# 5V_Stepdown.net
KiCad netlist of a schematic drawn in EAGLE
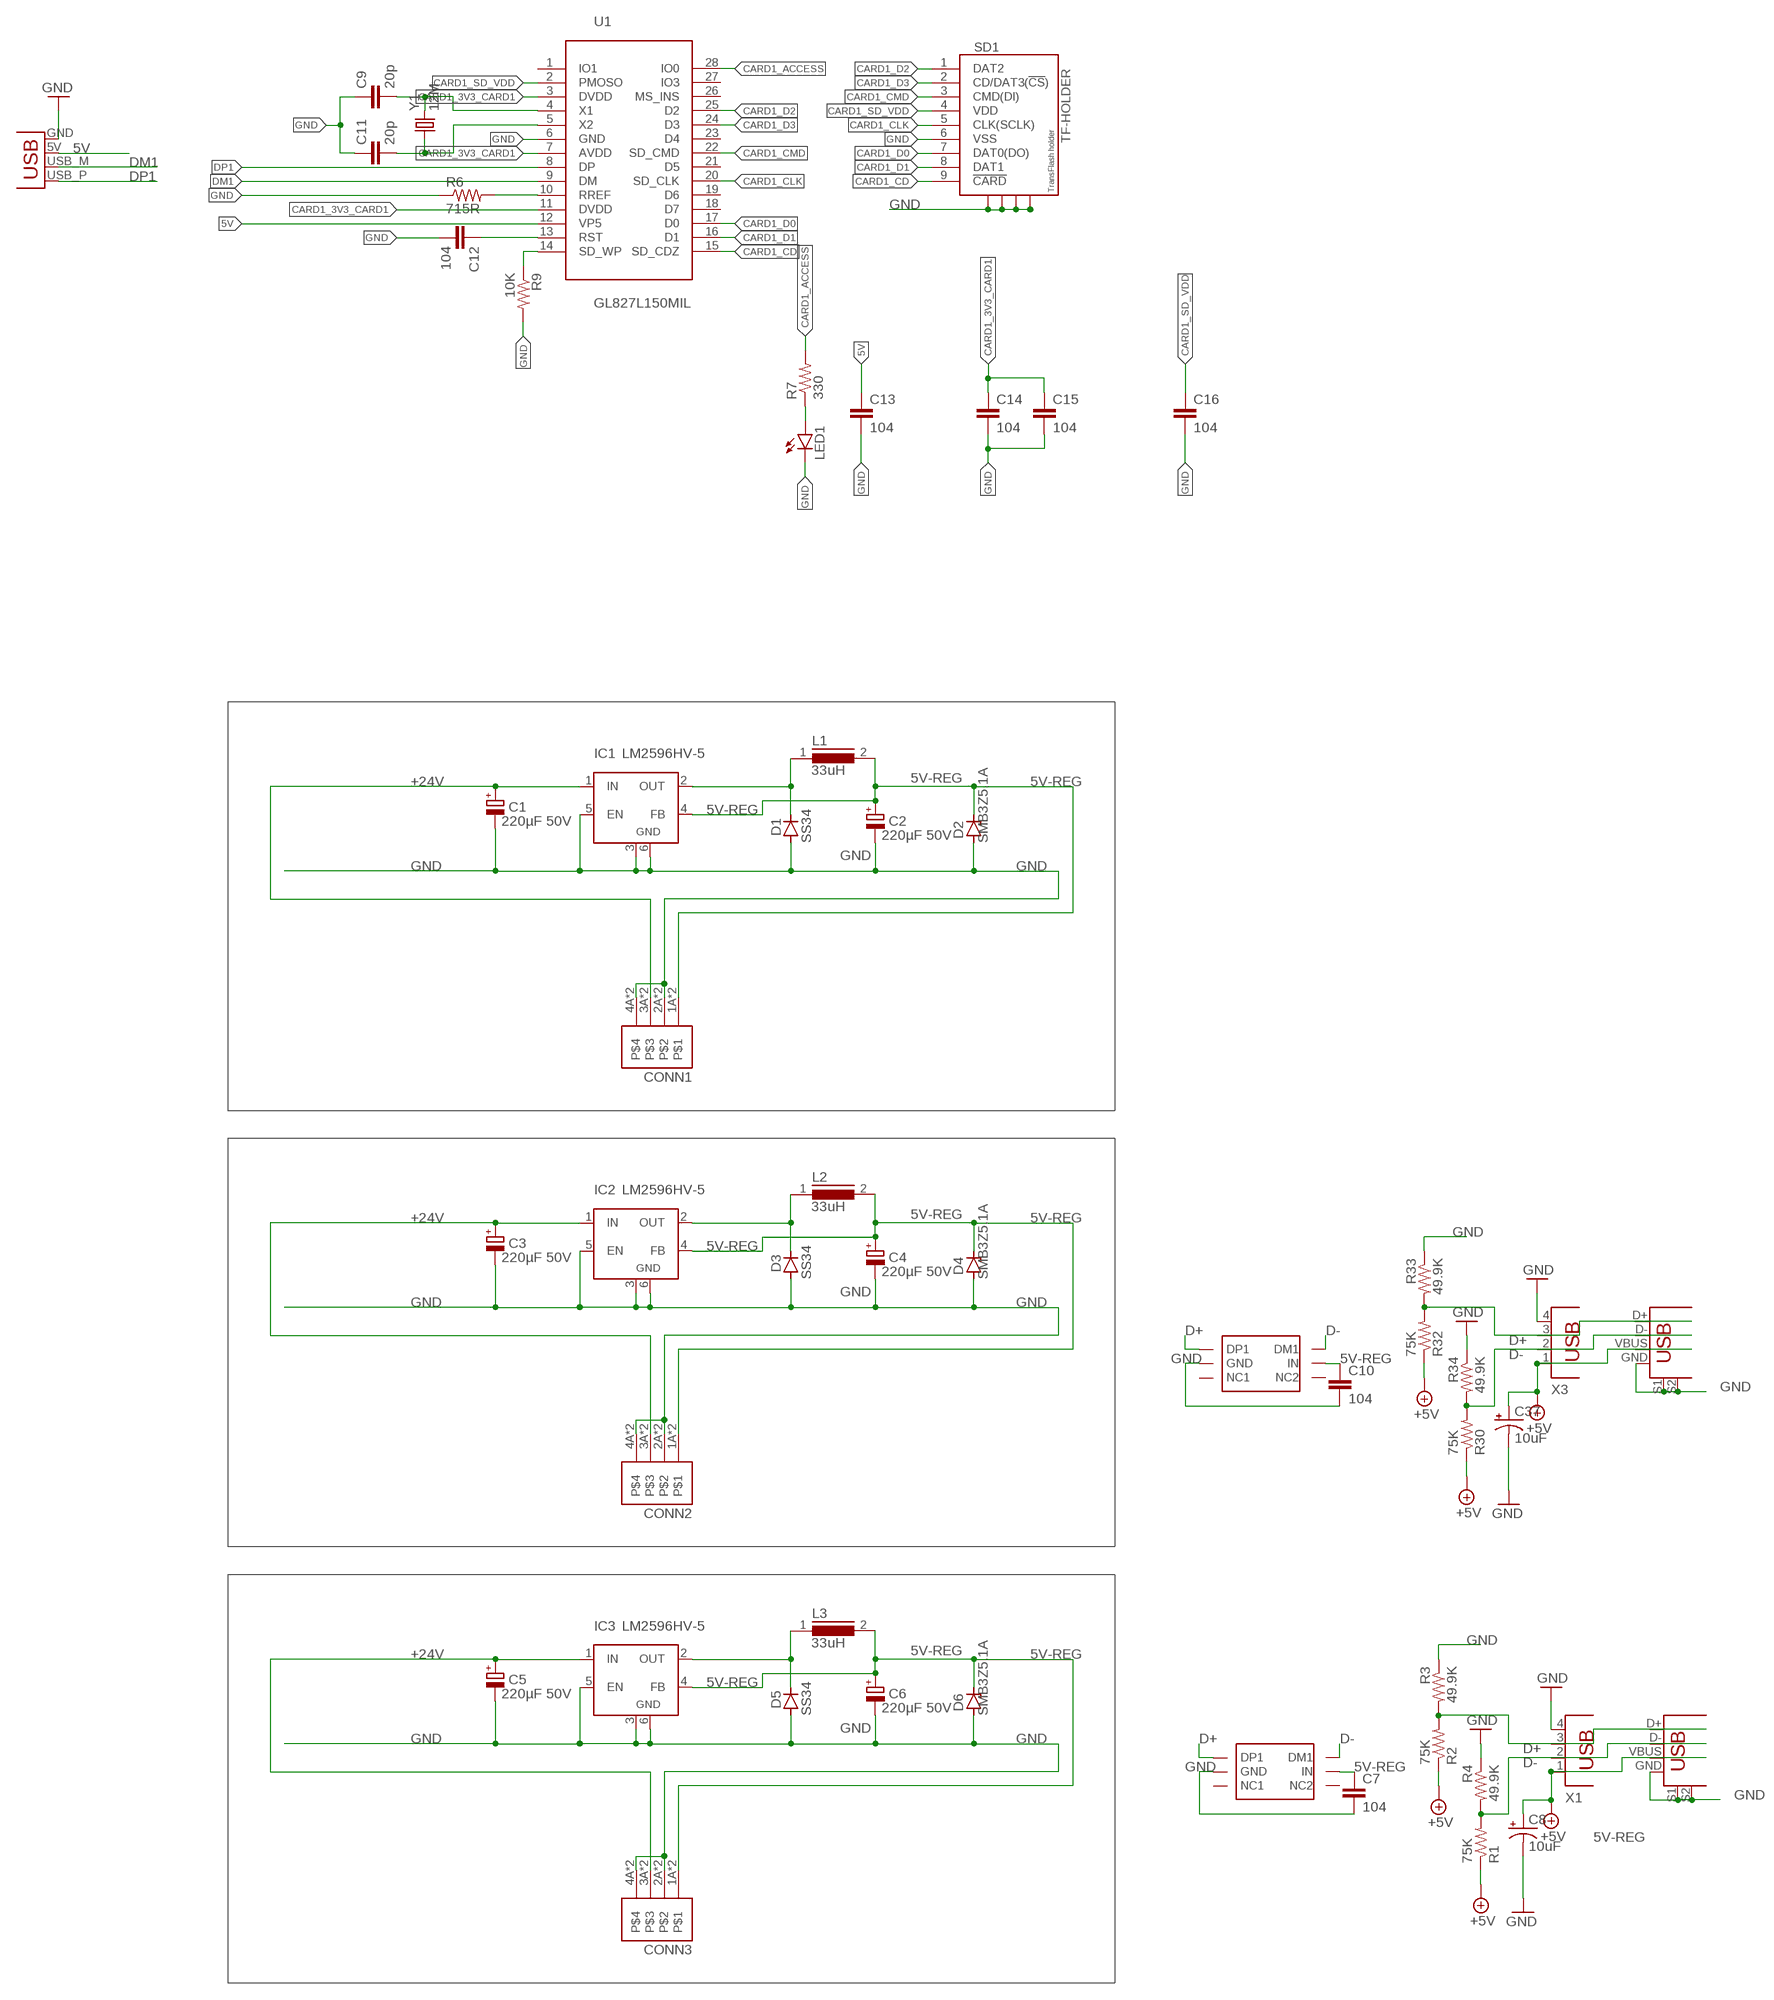
[diagram p0: schematic, sheet 1]

(export (version "E")
  (design (tool "Eeschema 10.0.6"))
  (components
    (comp (ref "C1")
      (value "220µF 50V")
      (footprint "eagle-import:PANASONIC_E")
      (libsource (lib "eagle-import") (part "CPOL-EUE"))
    )
    (comp (ref "C2")
      (value "220µF 50V")
      (footprint "eagle-import:PANASONIC_E")
      (libsource (lib "eagle-import") (part "CPOL-EUE"))
    )
    (comp (ref "C3")
      (value "220µF 50V")
      (footprint "eagle-import:PANASONIC_E")
      (libsource (lib "eagle-import") (part "CPOL-EUE"))
    )
    (comp (ref "C4")
      (value "220µF 50V")
      (footprint "eagle-import:PANASONIC_E")
      (libsource (lib "eagle-import") (part "CPOL-EUE"))
    )
    (comp (ref "C5")
      (value "220µF 50V")
      (footprint "eagle-import:PANASONIC_E")
      (libsource (lib "eagle-import") (part "CPOL-EUE"))
    )
    (comp (ref "C6")
      (value "220µF 50V")
      (footprint "eagle-import:PANASONIC_E")
      (libsource (lib "eagle-import") (part "CPOL-EUE"))
    )
    (comp (ref "C7")
      (value "104")
      (footprint "eagle-import:C1206")
      (libsource (lib "eagle-import") (part "C-EUC1206"))
    )
    (comp (ref "C8")
      (value "10uF")
      (footprint "eagle-import:EIA3216")
      (libsource (lib "eagle-import") (part "CAP_POL1206"))
    )
    (comp (ref "C9")
      (value "20p")
      (footprint "eagle-import:1206")
      (libsource (lib "eagle-import") (part "CAP1206"))
    )
    (comp (ref "C10")
      (value "104")
      (footprint "eagle-import:C1206")
      (libsource (lib "eagle-import") (part "C-EUC1206"))
    )
    (comp (ref "C11")
      (value "20p")
      (footprint "eagle-import:1206")
      (libsource (lib "eagle-import") (part "CAP1206"))
    )
    (comp (ref "C12")
      (value "104")
      (footprint "eagle-import:1206")
      (libsource (lib "eagle-import") (part "CAP1206"))
    )
    (comp (ref "C13")
      (value "104")
      (footprint "eagle-import:1206")
      (libsource (lib "eagle-import") (part "CAP1206"))
    )
    (comp (ref "C14")
      (value "104")
      (footprint "eagle-import:1206")
      (libsource (lib "eagle-import") (part "CAP1206"))
    )
    (comp (ref "C15")
      (value "104")
      (footprint "eagle-import:1206")
      (libsource (lib "eagle-import") (part "CAP1206"))
    )
    (comp (ref "C16")
      (value "104")
      (footprint "eagle-import:1206")
      (libsource (lib "eagle-import") (part "CAP1206"))
    )
    (comp (ref "C37")
      (value "10uF")
      (footprint "eagle-import:EIA3216")
      (libsource (lib "eagle-import") (part "CAP_POL1206"))
    )
    (comp (ref "CONN1")
      (value "WJ212R-THR-3.5-4")
      (footprint "eagle-import:WJ212R-THR-3.5-4")
      (libsource (lib "eagle-import") (part "WJ212R-THR-3.5-4"))
    )
    (comp (ref "CONN2")
      (value "WJ212R-THR-3.5-4")
      (footprint "eagle-import:WJ212R-THR-3.5-4")
      (libsource (lib "eagle-import") (part "WJ212R-THR-3.5-4"))
    )
    (comp (ref "CONN3")
      (value "WJ212R-THR-3.5-4")
      (footprint "eagle-import:WJ212R-THR-3.5-4")
      (libsource (lib "eagle-import") (part "WJ212R-THR-3.5-4"))
    )
    (comp (ref "D1")
      (value "SS34")
      (footprint "eagle-import:SOD87")
      (libsource (lib "eagle-import") (part "D-SOD-87"))
    )
    (comp (ref "D2")
      (value "SMB3Z5.1A")
      (footprint "eagle-import:SMB")
      (libsource (lib "eagle-import") (part "ZENER-DIODESMB"))
    )
    (comp (ref "D3")
      (value "SS34")
      (footprint "eagle-import:SOD87")
      (libsource (lib "eagle-import") (part "D-SOD-87"))
    )
    (comp (ref "D4")
      (value "SMB3Z5.1A")
      (footprint "eagle-import:SMB")
      (libsource (lib "eagle-import") (part "ZENER-DIODESMB"))
    )
    (comp (ref "D5")
      (value "SS34")
      (footprint "eagle-import:SOD87")
      (libsource (lib "eagle-import") (part "D-SOD-87"))
    )
    (comp (ref "D6")
      (value "SMB3Z5.1A")
      (footprint "eagle-import:SMB")
      (libsource (lib "eagle-import") (part "ZENER-DIODESMB"))
    )
    (comp (ref "IC1")
      (value "LM2596HV-5")
      (footprint "eagle-import:TO263-5")
      (libsource (lib "eagle-import") (part "LM2596S"))
    )
    (comp (ref "IC2")
      (value "LM2596HV-5")
      (footprint "eagle-import:TO263-5")
      (libsource (lib "eagle-import") (part "LM2596S"))
    )
    (comp (ref "IC3")
      (value "LM2596HV-5")
      (footprint "eagle-import:TO263-5")
      (libsource (lib "eagle-import") (part "LM2596S"))
    )
    (comp (ref "L1")
      (value "33uH")
      (footprint "eagle-import:DR127")
      (libsource (lib "eagle-import") (part "DR127"))
    )
    (comp (ref "L2")
      (value "33uH")
      (footprint "eagle-import:DR127")
      (libsource (lib "eagle-import") (part "DR127"))
    )
    (comp (ref "L3")
      (value "33uH")
      (footprint "eagle-import:DR127")
      (libsource (lib "eagle-import") (part "DR127"))
    )
    (comp (ref "LED1")
      (value "LED3MM")
      (footprint "eagle-import:LED3MM")
      (libsource (lib "eagle-import") (part "LED3MM"))
    )
    (comp (ref "R1")
      (value "75K")
      (footprint "eagle-import:M1206")
      (libsource (lib "eagle-import") (part "R-US_M1206"))
    )
    (comp (ref "R2")
      (value "75K")
      (footprint "eagle-import:M1206")
      (libsource (lib "eagle-import") (part "R-US_M1206"))
    )
    (comp (ref "R3")
      (value "49.9K")
      (footprint "eagle-import:M1206")
      (libsource (lib "eagle-import") (part "R-US_M1206"))
    )
    (comp (ref "R4")
      (value "49.9K")
      (footprint "eagle-import:M1206")
      (libsource (lib "eagle-import") (part "R-US_M1206"))
    )
    (comp (ref "R6")
      (value "715R")
      (footprint "eagle-import:1206")
      (libsource (lib "eagle-import") (part "RESISTOR1206"))
    )
    (comp (ref "R7")
      (value "330")
      (footprint "eagle-import:1206")
      (libsource (lib "eagle-import") (part "RESISTOR1206"))
    )
    (comp (ref "R9")
      (value "10K")
      (footprint "eagle-import:1206")
      (libsource (lib "eagle-import") (part "RESISTOR1206"))
    )
    (comp (ref "R30")
      (value "75K")
      (footprint "eagle-import:M1206")
      (libsource (lib "eagle-import") (part "R-US_M1206"))
    )
    (comp (ref "R32")
      (value "75K")
      (footprint "eagle-import:M1206")
      (libsource (lib "eagle-import") (part "R-US_M1206"))
    )
    (comp (ref "R33")
      (value "49.9K")
      (footprint "eagle-import:M1206")
      (libsource (lib "eagle-import") (part "R-US_M1206"))
    )
    (comp (ref "R34")
      (value "49.9K")
      (footprint "eagle-import:M1206")
      (libsource (lib "eagle-import") (part "R-US_M1206"))
    )
    (comp (ref "SD1")
      (value "TF-HOLDER")
      (footprint "eagle-import:TF-PULL")
      (libsource (lib "eagle-import") (part "TF-HOLDER"))
    )
    (comp (ref "U$1")
      (value "TPS2514")
      (footprint "eagle-import:TPS2514")
      (libsource (lib "eagle-import") (part "TPS2514"))
    )
    (comp (ref "U$2")
      (value "TPS2514")
      (footprint "eagle-import:TPS2514")
      (libsource (lib "eagle-import") (part "TPS2514"))
    )
    (comp (ref "U$3")
      (value "USB+SHIELDUSB-A-S-NOSILK-FEMALE")
      (footprint "eagle-import:USB-A-S-NOSILK-FEMALE")
      (libsource (lib "eagle-import") (part "USB+SHIELDUSB-A-S-NOSILK-FEMALE"))
    )
    (comp (ref "U$4")
      (value "USB+SHIELDUSB-A-S-NOSILK-FEMALE")
      (footprint "eagle-import:USB-A-S-NOSILK-FEMALE")
      (libsource (lib "eagle-import") (part "USB+SHIELDUSB-A-S-NOSILK-FEMALE"))
    )
    (comp (ref "U1")
      (value "GL827L150MIL")
      (footprint "eagle-import:SSOP28-39")
      (libsource (lib "eagle-import") (part "GL827L150MIL"))
    )
    (comp (ref "X1")
      (value "PN87520")
      (footprint "eagle-import:PN87520")
      (libsource (lib "eagle-import") (part "PN87520"))
    )
    (comp (ref "X2")
      (value "USBPCB")
      (footprint "eagle-import:USB-A-PCB")
      (libsource (lib "eagle-import") (part "USBPCB"))
    )
    (comp (ref "X3")
      (value "PN87520")
      (footprint "eagle-import:PN87520")
      (libsource (lib "eagle-import") (part "PN87520"))
    )
    (comp (ref "Y1")
      (value "12M")
      (footprint "eagle-import:HC49US")
      (libsource (lib "eagle-import") (part "CRYSTAL2HC49US"))
    )
  )
  (nets
    (net (code "1") (name "+24V") (class "Default")
      (node (ref "C1") (pin "+") (pinfunction "+_+") (pintype "passive"))
      (node (ref "C3") (pin "+") (pinfunction "+_+") (pintype "passive"))
      (node (ref "C5") (pin "+") (pinfunction "+_+") (pintype "passive"))
      (node (ref "CONN1") (pin "3A") (pinfunction "P$3_3A") (pintype "bidirectional"))
      (node (ref "CONN1") (pin "3B") (pinfunction "P$3_3B") (pintype "bidirectional"))
      (node (ref "CONN2") (pin "3A") (pinfunction "P$3_3A") (pintype "bidirectional"))
      (node (ref "CONN2") (pin "3B") (pinfunction "P$3_3B") (pintype "bidirectional"))
      (node (ref "CONN3") (pin "3A") (pinfunction "P$3_3A") (pintype "bidirectional"))
      (node (ref "CONN3") (pin "3B") (pinfunction "P$3_3B") (pintype "bidirectional"))
      (node (ref "IC1") (pin "1") (pinfunction "IN_1") (pintype "input"))
      (node (ref "IC2") (pin "1") (pinfunction "IN_1") (pintype "input"))
      (node (ref "IC3") (pin "1") (pinfunction "IN_1") (pintype "input"))
    )
    (net (code "2") (name "5V") (class "Default")
      (node (ref "C13") (pin "1") (pinfunction "1_1") (pintype "passive"))
      (node (ref "U1") (pin "12") (pinfunction "VP5_12") (pintype "bidirectional"))
      (node (ref "X2") (pin "5V") (pinfunction "VBUS_5V") (pintype "bidirectional"))
    )
    (net (code "3") (name "5V-REG") (class "Default")
      (node (ref "C10") (pin "1") (pinfunction "1_1") (pintype "passive"))
      (node (ref "C2") (pin "+") (pinfunction "+_+") (pintype "passive"))
      (node (ref "C37") (pin "A") (pinfunction "+_A") (pintype "passive"))
      (node (ref "C4") (pin "+") (pinfunction "+_+") (pintype "passive"))
      (node (ref "C6") (pin "+") (pinfunction "+_+") (pintype "passive"))
      (node (ref "C7") (pin "1") (pinfunction "1_1") (pintype "passive"))
      (node (ref "C8") (pin "A") (pinfunction "+_A") (pintype "passive"))
      (node (ref "CONN1") (pin "1A") (pinfunction "P$1_1A") (pintype "bidirectional"))
      (node (ref "CONN1") (pin "1B") (pinfunction "P$1_1B") (pintype "bidirectional"))
      (node (ref "CONN2") (pin "1A") (pinfunction "P$1_1A") (pintype "bidirectional"))
      (node (ref "CONN2") (pin "1B") (pinfunction "P$1_1B") (pintype "bidirectional"))
      (node (ref "CONN3") (pin "1A") (pinfunction "P$1_1A") (pintype "bidirectional"))
      (node (ref "CONN3") (pin "1B") (pinfunction "P$1_1B") (pintype "bidirectional"))
      (node (ref "D2") (pin "C") (pinfunction "C_C") (pintype "passive"))
      (node (ref "D4") (pin "C") (pinfunction "C_C") (pintype "passive"))
      (node (ref "D6") (pin "C") (pinfunction "C_C") (pintype "passive"))
      (node (ref "IC1") (pin "4") (pinfunction "FB_4") (pintype "input"))
      (node (ref "IC2") (pin "4") (pinfunction "FB_4") (pintype "input"))
      (node (ref "IC3") (pin "4") (pinfunction "FB_4") (pintype "input"))
      (node (ref "L1") (pin "2") (pinfunction "2_2") (pintype "passive"))
      (node (ref "L2") (pin "2") (pinfunction "2_2") (pintype "passive"))
      (node (ref "L3") (pin "2") (pinfunction "2_2") (pintype "passive"))
      (node (ref "R1") (pin "1") (pinfunction "1_1") (pintype "passive"))
      (node (ref "R2") (pin "1") (pinfunction "1_1") (pintype "passive"))
      (node (ref "R30") (pin "1") (pinfunction "1_1") (pintype "passive"))
      (node (ref "R32") (pin "1") (pinfunction "1_1") (pintype "passive"))
      (node (ref "U$1") (pin "IN") (pinfunction "IN_IN") (pintype "bidirectional"))
      (node (ref "U$2") (pin "IN") (pinfunction "IN_IN") (pintype "bidirectional"))
      (node (ref "U$3") (pin "VBUS") (pinfunction "VBUS_VBUS") (pintype "bidirectional"))
      (node (ref "U$4") (pin "VBUS") (pinfunction "VBUS_VBUS") (pintype "bidirectional"))
      (node (ref "X1") (pin "1") (pinfunction "1_1") (pintype "passive"))
      (node (ref "X3") (pin "1") (pinfunction "1_1") (pintype "passive"))
    )
    (net (code "4") (name "CARD1_3V3_CARD1") (class "Default")
      (node (ref "C14") (pin "1") (pinfunction "1_1") (pintype "passive"))
      (node (ref "C15") (pin "1") (pinfunction "1_1") (pintype "passive"))
      (node (ref "U1") (pin "11") (pinfunction "DVDD_11") (pintype "bidirectional"))
      (node (ref "U1") (pin "3") (pinfunction "DVDD_3") (pintype "bidirectional"))
      (node (ref "U1") (pin "7") (pinfunction "AVDD_7") (pintype "bidirectional"))
    )
    (net (code "5") (name "CARD1_ACCESS") (class "Default")
      (node (ref "R7") (pin "2") (pinfunction "2_2") (pintype "passive"))
      (node (ref "U1") (pin "28") (pinfunction "IO0_28") (pintype "bidirectional"))
    )
    (net (code "6") (name "CARD1_CD") (class "Default")
      (node (ref "SD1") (pin "9") (pinfunction "~{CARD}_9") (pintype "passive"))
      (node (ref "U1") (pin "15") (pinfunction "SD_CDZ_15") (pintype "bidirectional"))
    )
    (net (code "7") (name "CARD1_CLK") (class "Default")
      (node (ref "SD1") (pin "5") (pinfunction "CLK(SCLK)_5") (pintype "input"))
      (node (ref "U1") (pin "20") (pinfunction "SD_CLK_20") (pintype "bidirectional"))
    )
    (net (code "8") (name "CARD1_CMD") (class "Default")
      (node (ref "SD1") (pin "3") (pinfunction "CMD(DI)_3") (pintype "bidirectional"))
      (node (ref "U1") (pin "22") (pinfunction "SD_CMD_22") (pintype "bidirectional"))
    )
    (net (code "9") (name "CARD1_D0") (class "Default")
      (node (ref "SD1") (pin "7") (pinfunction "DAT0(DO)_7") (pintype "bidirectional"))
      (node (ref "U1") (pin "17") (pinfunction "D0_17") (pintype "bidirectional"))
    )
    (net (code "10") (name "CARD1_D1") (class "Default")
      (node (ref "SD1") (pin "8") (pinfunction "DAT1_8") (pintype "bidirectional"))
      (node (ref "U1") (pin "16") (pinfunction "D1_16") (pintype "bidirectional"))
    )
    (net (code "11") (name "CARD1_D2") (class "Default")
      (node (ref "SD1") (pin "1") (pinfunction "DAT2_1") (pintype "bidirectional"))
      (node (ref "U1") (pin "25") (pinfunction "D2_25") (pintype "bidirectional"))
    )
    (net (code "12") (name "CARD1_D3") (class "Default")
      (node (ref "SD1") (pin "2") (pinfunction "CD/DAT3(~{CS})_2") (pintype "bidirectional"))
      (node (ref "U1") (pin "24") (pinfunction "D3_24") (pintype "bidirectional"))
    )
    (net (code "13") (name "CARD1_SD_VDD") (class "Default")
      (node (ref "C16") (pin "1") (pinfunction "1_1") (pintype "passive"))
      (node (ref "SD1") (pin "4") (pinfunction "VDD_4") (pintype "power_in"))
      (node (ref "U1") (pin "2") (pinfunction "PMOSO_2") (pintype "bidirectional"))
    )
    (net (code "14") (name "D+") (class "Default")
      (node (ref "R2") (pin "2") (pinfunction "2_2") (pintype "passive"))
      (node (ref "R3") (pin "2") (pinfunction "2_2") (pintype "passive"))
      (node (ref "R32") (pin "2") (pinfunction "2_2") (pintype "passive"))
      (node (ref "R33") (pin "2") (pinfunction "2_2") (pintype "passive"))
      (node (ref "U$1") (pin "DP1") (pinfunction "DP1_DP1") (pintype "bidirectional"))
      (node (ref "U$2") (pin "DP1") (pinfunction "DP1_DP1") (pintype "bidirectional"))
      (node (ref "U$3") (pin "D+") (pinfunction "D+_D+") (pintype "bidirectional"))
      (node (ref "U$4") (pin "D+") (pinfunction "D+_D+") (pintype "bidirectional"))
      (node (ref "X1") (pin "3") (pinfunction "3_3") (pintype "passive"))
      (node (ref "X3") (pin "3") (pinfunction "3_3") (pintype "passive"))
    )
    (net (code "15") (name "D-") (class "Default")
      (node (ref "R1") (pin "2") (pinfunction "2_2") (pintype "passive"))
      (node (ref "R30") (pin "2") (pinfunction "2_2") (pintype "passive"))
      (node (ref "R34") (pin "2") (pinfunction "2_2") (pintype "passive"))
      (node (ref "R4") (pin "2") (pinfunction "2_2") (pintype "passive"))
      (node (ref "U$1") (pin "DM1") (pinfunction "DM1_DM1") (pintype "bidirectional"))
      (node (ref "U$2") (pin "DM1") (pinfunction "DM1_DM1") (pintype "bidirectional"))
      (node (ref "U$3") (pin "D-") (pinfunction "D-_D-") (pintype "bidirectional"))
      (node (ref "U$4") (pin "D-") (pinfunction "D-_D-") (pintype "bidirectional"))
      (node (ref "X1") (pin "2") (pinfunction "2_2") (pintype "passive"))
      (node (ref "X3") (pin "2") (pinfunction "2_2") (pintype "passive"))
    )
    (net (code "16") (name "DM1") (class "Default")
      (node (ref "U1") (pin "9") (pinfunction "DM_9") (pintype "bidirectional"))
      (node (ref "X2") (pin "USB_M") (pinfunction "D-_USB_M") (pintype "bidirectional"))
    )
    (net (code "17") (name "DP1") (class "Default")
      (node (ref "U1") (pin "8") (pinfunction "DP_8") (pintype "bidirectional"))
      (node (ref "X2") (pin "USB_P") (pinfunction "D+_USB_P") (pintype "bidirectional"))
    )
    (net (code "18") (name "GND") (class "Default")
      (node (ref "C1") (pin "-") (pinfunction "-_-") (pintype "passive"))
      (node (ref "C10") (pin "2") (pinfunction "2_2") (pintype "passive"))
      (node (ref "C11") (pin "1") (pinfunction "1_1") (pintype "passive"))
      (node (ref "C12") (pin "2") (pinfunction "2_2") (pintype "passive"))
      (node (ref "C13") (pin "2") (pinfunction "2_2") (pintype "passive"))
      (node (ref "C14") (pin "2") (pinfunction "2_2") (pintype "passive"))
      (node (ref "C15") (pin "2") (pinfunction "2_2") (pintype "passive"))
      (node (ref "C16") (pin "2") (pinfunction "2_2") (pintype "passive"))
      (node (ref "C2") (pin "-") (pinfunction "-_-") (pintype "passive"))
      (node (ref "C3") (pin "-") (pinfunction "-_-") (pintype "passive"))
      (node (ref "C37") (pin "C") (pinfunction "-_C") (pintype "passive"))
      (node (ref "C4") (pin "-") (pinfunction "-_-") (pintype "passive"))
      (node (ref "C5") (pin "-") (pinfunction "-_-") (pintype "passive"))
      (node (ref "C6") (pin "-") (pinfunction "-_-") (pintype "passive"))
      (node (ref "C7") (pin "2") (pinfunction "2_2") (pintype "passive"))
      (node (ref "C8") (pin "C") (pinfunction "-_C") (pintype "passive"))
      (node (ref "C9") (pin "1") (pinfunction "1_1") (pintype "passive"))
      (node (ref "CONN1") (pin "2A") (pinfunction "P$2_2A") (pintype "bidirectional"))
      (node (ref "CONN1") (pin "2B") (pinfunction "P$2_2B") (pintype "bidirectional"))
      (node (ref "CONN1") (pin "4A") (pinfunction "P$4_4A") (pintype "bidirectional"))
      (node (ref "CONN1") (pin "4B") (pinfunction "P$4_4B") (pintype "bidirectional"))
      (node (ref "CONN2") (pin "2A") (pinfunction "P$2_2A") (pintype "bidirectional"))
      (node (ref "CONN2") (pin "2B") (pinfunction "P$2_2B") (pintype "bidirectional"))
      (node (ref "CONN2") (pin "4A") (pinfunction "P$4_4A") (pintype "bidirectional"))
      (node (ref "CONN2") (pin "4B") (pinfunction "P$4_4B") (pintype "bidirectional"))
      (node (ref "CONN3") (pin "2A") (pinfunction "P$2_2A") (pintype "bidirectional"))
      (node (ref "CONN3") (pin "2B") (pinfunction "P$2_2B") (pintype "bidirectional"))
      (node (ref "CONN3") (pin "4A") (pinfunction "P$4_4A") (pintype "bidirectional"))
      (node (ref "CONN3") (pin "4B") (pinfunction "P$4_4B") (pintype "bidirectional"))
      (node (ref "D1") (pin "2") (pinfunction "A_2") (pintype "passive"))
      (node (ref "D2") (pin "A") (pinfunction "A_A") (pintype "passive"))
      (node (ref "D3") (pin "2") (pinfunction "A_2") (pintype "passive"))
      (node (ref "D4") (pin "A") (pinfunction "A_A") (pintype "passive"))
      (node (ref "D5") (pin "2") (pinfunction "A_2") (pintype "passive"))
      (node (ref "D6") (pin "A") (pinfunction "A_A") (pintype "passive"))
      (node (ref "IC1") (pin "3") (pinfunction "GND_3") (pintype "power_in"))
      (node (ref "IC1") (pin "5") (pinfunction "EN_5") (pintype "input"))
      (node (ref "IC1") (pin "6") (pinfunction "GND_6") (pintype "power_in"))
      (node (ref "IC2") (pin "3") (pinfunction "GND_3") (pintype "power_in"))
      (node (ref "IC2") (pin "5") (pinfunction "EN_5") (pintype "input"))
      (node (ref "IC2") (pin "6") (pinfunction "GND_6") (pintype "power_in"))
      (node (ref "IC3") (pin "3") (pinfunction "GND_3") (pintype "power_in"))
      (node (ref "IC3") (pin "5") (pinfunction "EN_5") (pintype "input"))
      (node (ref "IC3") (pin "6") (pinfunction "GND_6") (pintype "power_in"))
      (node (ref "LED1") (pin "K") (pinfunction "C_K") (pintype "passive"))
      (node (ref "R3") (pin "1") (pinfunction "1_1") (pintype "passive"))
      (node (ref "R33") (pin "1") (pinfunction "1_1") (pintype "passive"))
      (node (ref "R34") (pin "1") (pinfunction "1_1") (pintype "passive"))
      (node (ref "R4") (pin "1") (pinfunction "1_1") (pintype "passive"))
      (node (ref "R6") (pin "1") (pinfunction "1_1") (pintype "passive"))
      (node (ref "R9") (pin "2") (pinfunction "2_2") (pintype "passive"))
      (node (ref "SD1") (pin "6") (pinfunction "VSS_6") (pintype "power_in"))
      (node (ref "SD1") (pin "S1") (pinfunction "S1_S1") (pintype "passive"))
      (node (ref "SD1") (pin "S2") (pinfunction "S2_S2") (pintype "passive"))
      (node (ref "SD1") (pin "S3") (pinfunction "S3_S3") (pintype "passive"))
      (node (ref "SD1") (pin "S4") (pinfunction "S4_S4") (pintype "passive"))
      (node (ref "U$1") (pin "GND") (pinfunction "GND_GND") (pintype "bidirectional"))
      (node (ref "U$2") (pin "GND") (pinfunction "GND_GND") (pintype "bidirectional"))
      (node (ref "U$3") (pin "GND") (pinfunction "GND_GND") (pintype "bidirectional"))
      (node (ref "U$3") (pin "S1") (pinfunction "S1_S1") (pintype "bidirectional"))
      (node (ref "U$3") (pin "S2") (pinfunction "S2_S2") (pintype "bidirectional"))
      (node (ref "U$4") (pin "GND") (pinfunction "GND_GND") (pintype "bidirectional"))
      (node (ref "U$4") (pin "S1") (pinfunction "S1_S1") (pintype "bidirectional"))
      (node (ref "U$4") (pin "S2") (pinfunction "S2_S2") (pintype "bidirectional"))
      (node (ref "U1") (pin "6") (pinfunction "GND_6") (pintype "bidirectional"))
      (node (ref "X1") (pin "4") (pinfunction "4_4") (pintype "passive"))
      (node (ref "X2") (pin "GND") (pinfunction "GND_GND") (pintype "bidirectional"))
      (node (ref "X3") (pin "4") (pinfunction "4_4") (pintype "passive"))
    )
    (net (code "19") (name "Net-(D1-C)") (class "Default")
      (node (ref "D1") (pin "1") (pinfunction "C_1") (pintype "passive"))
      (node (ref "IC1") (pin "2") (pinfunction "OUT_2") (pintype "output"))
      (node (ref "L1") (pin "1") (pinfunction "1_1") (pintype "passive"))
    )
    (net (code "20") (name "Net-(D3-C)") (class "Default")
      (node (ref "D3") (pin "1") (pinfunction "C_1") (pintype "passive"))
      (node (ref "IC2") (pin "2") (pinfunction "OUT_2") (pintype "output"))
      (node (ref "L2") (pin "1") (pinfunction "1_1") (pintype "passive"))
    )
    (net (code "21") (name "Net-(D5-C)") (class "Default")
      (node (ref "D5") (pin "1") (pinfunction "C_1") (pintype "passive"))
      (node (ref "IC3") (pin "2") (pinfunction "OUT_2") (pintype "output"))
      (node (ref "L3") (pin "1") (pinfunction "1_1") (pintype "passive"))
    )
    (net (code "22") (name "Net-(LED1-PadA)") (class "Default")
      (node (ref "LED1") (pin "A") (pinfunction "A_A") (pintype "passive"))
      (node (ref "R7") (pin "1") (pinfunction "1_1") (pintype "passive"))
    )
    (net (code "23") (name "Net-(U1-RREF)") (class "Default")
      (node (ref "R6") (pin "2") (pinfunction "2_2") (pintype "passive"))
      (node (ref "U1") (pin "10") (pinfunction "RREF_10") (pintype "bidirectional"))
    )
    (net (code "24") (name "Net-(U1-RST)") (class "Default")
      (node (ref "C12") (pin "1") (pinfunction "1_1") (pintype "passive"))
      (node (ref "U1") (pin "13") (pinfunction "RST_13") (pintype "bidirectional"))
    )
    (net (code "25") (name "Net-(U1-SD_WP)") (class "Default")
      (node (ref "R9") (pin "1") (pinfunction "1_1") (pintype "passive"))
      (node (ref "U1") (pin "14") (pinfunction "SD_WP_14") (pintype "bidirectional"))
    )
    (net (code "26") (name "Net-(U1-X1)") (class "Default")
      (node (ref "C9") (pin "2") (pinfunction "2_2") (pintype "passive"))
      (node (ref "U1") (pin "4") (pinfunction "X1_4") (pintype "bidirectional"))
      (node (ref "Y1") (pin "2") (pinfunction "2_2") (pintype "passive"))
    )
    (net (code "27") (name "Net-(U1-X2)") (class "Default")
      (node (ref "C11") (pin "2") (pinfunction "2_2") (pintype "passive"))
      (node (ref "U1") (pin "5") (pinfunction "X2_5") (pintype "bidirectional"))
      (node (ref "Y1") (pin "1") (pinfunction "1_1") (pintype "passive"))
    )
    (net (code "28") (name "unconnected-(U$1-NC1-PadNC)") (class "Default")
      (node (ref "U$1") (pin "NC") (pinfunction "NC1_NC") (pintype "bidirectional"))
    )
    (net (code "29") (name "unconnected-(U$1-PadNC2)") (class "Default")
      (node (ref "U$1") (pin "NC2") (pinfunction "NC2_NC2") (pintype "bidirectional"))
    )
    (net (code "30") (name "unconnected-(U$2-NC1-PadNC)") (class "Default")
      (node (ref "U$2") (pin "NC") (pinfunction "NC1_NC") (pintype "bidirectional"))
    )
    (net (code "31") (name "unconnected-(U$2-PadNC2)") (class "Default")
      (node (ref "U$2") (pin "NC2") (pinfunction "NC2_NC2") (pintype "bidirectional"))
    )
    (net (code "32") (name "unconnected-(U1-D4-Pad23)") (class "Default")
      (node (ref "U1") (pin "23") (pinfunction "D4_23") (pintype "bidirectional"))
    )
    (net (code "33") (name "unconnected-(U1-D5-Pad21)") (class "Default")
      (node (ref "U1") (pin "21") (pinfunction "D5_21") (pintype "bidirectional"))
    )
    (net (code "34") (name "unconnected-(U1-D6-Pad19)") (class "Default")
      (node (ref "U1") (pin "19") (pinfunction "D6_19") (pintype "bidirectional"))
    )
    (net (code "35") (name "unconnected-(U1-D7-Pad18)") (class "Default")
      (node (ref "U1") (pin "18") (pinfunction "D7_18") (pintype "bidirectional"))
    )
    (net (code "36") (name "unconnected-(U1-IO1-Pad1)") (class "Default")
      (node (ref "U1") (pin "1") (pinfunction "IO1_1") (pintype "bidirectional"))
    )
    (net (code "37") (name "unconnected-(U1-IO3-Pad27)") (class "Default")
      (node (ref "U1") (pin "27") (pinfunction "IO3_27") (pintype "bidirectional"))
    )
    (net (code "38") (name "unconnected-(U1-MS_INS-Pad26)") (class "Default")
      (node (ref "U1") (pin "26") (pinfunction "MS_INS_26") (pintype "bidirectional"))
    )
  )
)
